# project_vodorezov_switch3.net
KiCad netlist of a schematic drawn in Altium Designer
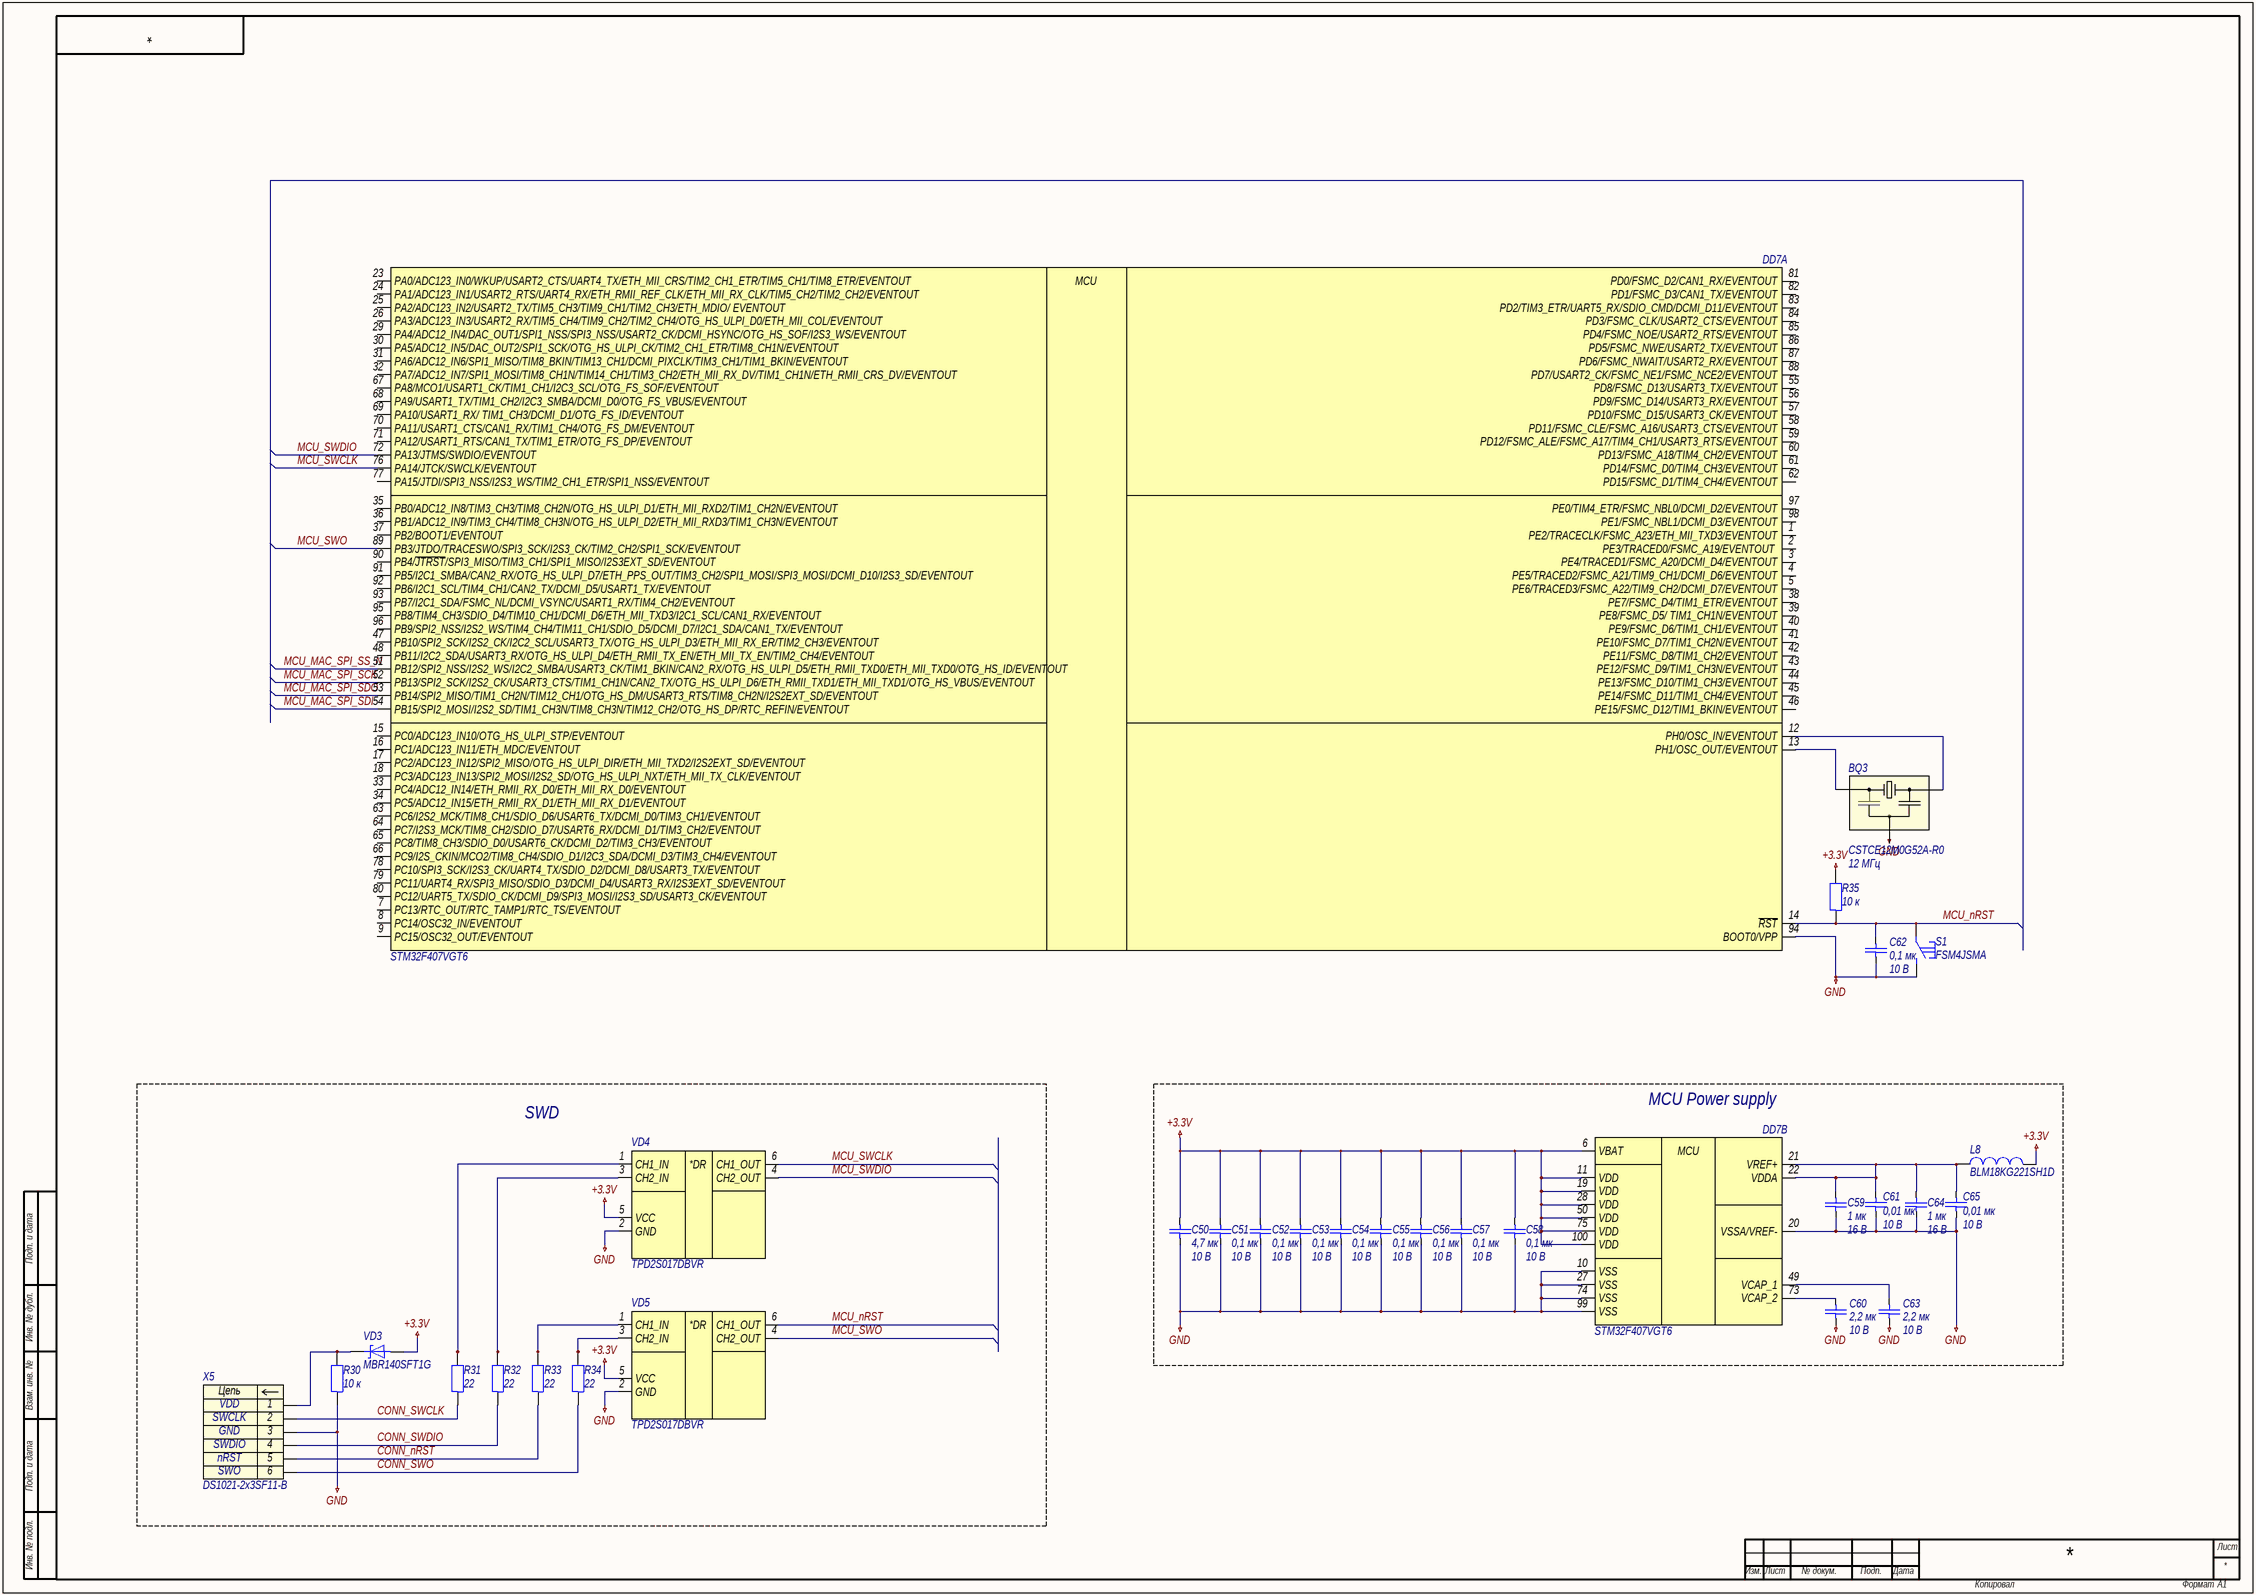
[diagram p0: project_vodorezov_switch3.SchDoc]

(export (version "E")
  (design (tool "Eeschema 10.0.6"))
  (components
    (comp (ref "BQ3")
      (value "CSTCE12M0G52A-R0")
      (footprint "CSTCE-3-P120-320X130X70")
      (description "=Описание")
      (fields (field (name "ЧАСТОТA") "12 МГц"))
      (libsource (lib "Database_Students") (part "CSTCE12M0G52A-R0"))
    )
    (comp (ref "C50")
      (value "4,7 мк")
      (footprint "C0603")
      (description "=Описание")
      (fields (field (name "НАПРЯЖЕНИЕ") "10 В"))
      (libsource (lib "Database_Students") (part "CAPACITOR-NONPOLAR"))
    )
    (comp (ref "C51")
      (value "0,1 мк")
      (footprint "C0402")
      (description "=Описание")
      (fields (field (name "НАПРЯЖЕНИЕ") "10 В"))
      (libsource (lib "Database_Students") (part "CAPACITOR-NONPOLAR"))
    )
    (comp (ref "C52")
      (value "0,1 мк")
      (footprint "C0402")
      (description "=Описание")
      (fields (field (name "НАПРЯЖЕНИЕ") "10 В"))
      (libsource (lib "Database_Students") (part "CAPACITOR-NONPOLAR"))
    )
    (comp (ref "C53")
      (value "0,1 мк")
      (footprint "C0402")
      (description "=Описание")
      (fields (field (name "НАПРЯЖЕНИЕ") "10 В"))
      (libsource (lib "Database_Students") (part "CAPACITOR-NONPOLAR"))
    )
    (comp (ref "C54")
      (value "0,1 мк")
      (footprint "C0402")
      (description "=Описание")
      (fields (field (name "НАПРЯЖЕНИЕ") "10 В"))
      (libsource (lib "Database_Students") (part "CAPACITOR-NONPOLAR"))
    )
    (comp (ref "C55")
      (value "0,1 мк")
      (footprint "C0402")
      (description "=Описание")
      (fields (field (name "НАПРЯЖЕНИЕ") "10 В"))
      (libsource (lib "Database_Students") (part "CAPACITOR-NONPOLAR"))
    )
    (comp (ref "C56")
      (value "0,1 мк")
      (footprint "C0402")
      (description "=Описание")
      (fields (field (name "НАПРЯЖЕНИЕ") "10 В"))
      (libsource (lib "Database_Students") (part "CAPACITOR-NONPOLAR"))
    )
    (comp (ref "C57")
      (value "0,1 мк")
      (footprint "C0402")
      (description "=Описание")
      (fields (field (name "НАПРЯЖЕНИЕ") "10 В"))
      (libsource (lib "Database_Students") (part "CAPACITOR-NONPOLAR"))
    )
    (comp (ref "C58")
      (value "0,1 мк")
      (footprint "C0402")
      (description "=Описание")
      (fields (field (name "НАПРЯЖЕНИЕ") "10 В"))
      (libsource (lib "Database_Students") (part "CAPACITOR-NONPOLAR"))
    )
    (comp (ref "C59")
      (value "1 мк")
      (footprint "C0603")
      (description "=Описание")
      (fields (field (name "НАПРЯЖЕНИЕ") "16 В"))
      (libsource (lib "Database_Students") (part "CAPACITOR-NONPOLAR"))
    )
    (comp (ref "C60")
      (value "2,2 мк")
      (footprint "C0603")
      (description "=Описание")
      (fields (field (name "НАПРЯЖЕНИЕ") "10 В"))
      (libsource (lib "Database_Students") (part "CAPACITOR-NONPOLAR"))
    )
    (comp (ref "C61")
      (value "0,01 мк")
      (footprint "C0603")
      (description "=Описание")
      (fields (field (name "НАПРЯЖЕНИЕ") "10 В"))
      (libsource (lib "Database_Students") (part "CAPACITOR-NONPOLAR"))
    )
    (comp (ref "C62")
      (value "0,1 мк")
      (footprint "C0603")
      (description "=Описание")
      (fields (field (name "НАПРЯЖЕНИЕ") "10 В"))
      (libsource (lib "Database_Students") (part "CAPACITOR-NONPOLAR"))
    )
    (comp (ref "C63")
      (value "2,2 мк")
      (footprint "C0603")
      (description "=Описание")
      (fields (field (name "НАПРЯЖЕНИЕ") "10 В"))
      (libsource (lib "Database_Students") (part "CAPACITOR-NONPOLAR"))
    )
    (comp (ref "C64")
      (value "1 мк")
      (footprint "C0603")
      (description "=Описание")
      (fields (field (name "НАПРЯЖЕНИЕ") "16 В"))
      (libsource (lib "Database_Students") (part "CAPACITOR-NONPOLAR"))
    )
    (comp (ref "C65")
      (value "0,01 мк")
      (footprint "C0603")
      (description "=Описание")
      (fields (field (name "НАПРЯЖЕНИЕ") "10 В"))
      (libsource (lib "Database_Students") (part "CAPACITOR-NONPOLAR"))
    )
    (comp (ref "DD7")
      (value "STM32F407VGT6")
      (footprint "LQFP-100-P50-1400X1400X160-L60X22")
      (description "=Описание")
      (libsource (lib "Database_Students") (part "STM32F407VGT6"))
    )
    (comp (ref "L8")
      (value "BLM18KG221SH1D")
      (footprint "BLM-2-0603")
      (description "=Описание")
      (libsource (lib "Database_Students") (part "FERRITE-BEAD"))
    )
    (comp (ref "R30")
      (value "10 к")
      (footprint "R0603")
      (description "=Описание")
      (libsource (lib "Database_Students") (part "RESISTOR-COMMON"))
    )
    (comp (ref "R31")
      (value "22")
      (footprint "R0603")
      (description "=Описание")
      (libsource (lib "Database_Students") (part "RESISTOR-COMMON"))
    )
    (comp (ref "R32")
      (value "22")
      (footprint "R0603")
      (description "=Описание")
      (libsource (lib "Database_Students") (part "RESISTOR-COMMON"))
    )
    (comp (ref "R33")
      (value "22")
      (footprint "R0603")
      (description "=Описание")
      (libsource (lib "Database_Students") (part "RESISTOR-COMMON"))
    )
    (comp (ref "R34")
      (value "22")
      (footprint "R0603")
      (description "=Описание")
      (libsource (lib "Database_Students") (part "RESISTOR-COMMON"))
    )
    (comp (ref "R35")
      (value "10 к")
      (footprint "R0603")
      (description "=Описание")
      (libsource (lib "Database_Students") (part "RESISTOR-COMMON"))
    )
    (comp (ref "S1")
      (value "FSM4JSMA")
      (footprint "FSM4JSMA")
      (description "=Описание")
      (libsource (lib "Database_Students") (part "BUTTON"))
    )
    (comp (ref "VD3")
      (value "MBR140SFT1G")
      (footprint "SOD-123FL-370X165X98")
      (description "=Описание")
      (libsource (lib "Database_Students") (part "DIODE-SCHOTTKY"))
    )
    (comp (ref "VD4")
      (value "TPD2S017DBVR")
      (footprint "SOT-23-6-P95-290X280X145")
      (description "=Описание")
      (libsource (lib "Database_Students") (part "TPD2S017DBVR"))
    )
    (comp (ref "VD5")
      (value "TPD2S017DBVR")
      (footprint "SOT-23-6-P95-290X280X145")
      (description "=Описание")
      (libsource (lib "Database_Students") (part "TPD2S017DBVR"))
    )
    (comp (ref "X5")
      (value "DS1021-2x3SF11-B")
      (footprint "DS1021-2X3SF11-B")
      (description "=Описание")
      (libsource (lib "Database_Students") (part "HEADER-6-PLG"))
    )
  )
  (nets
    (net (code "1") (name "+3.3V") (class "Default")
      (node (ref "C50") (pin "1") (pinfunction "1_1") (pintype "passive"))
      (node (ref "C51") (pin "1") (pinfunction "1_1") (pintype "passive"))
      (node (ref "C52") (pin "1") (pinfunction "1_1") (pintype "passive"))
      (node (ref "C53") (pin "1") (pinfunction "1_1") (pintype "passive"))
      (node (ref "C54") (pin "1") (pinfunction "1_1") (pintype "passive"))
      (node (ref "C55") (pin "1") (pinfunction "1_1") (pintype "passive"))
      (node (ref "C56") (pin "1") (pinfunction "1_1") (pintype "passive"))
      (node (ref "C57") (pin "1") (pinfunction "1_1") (pintype "passive"))
      (node (ref "C58") (pin "1") (pinfunction "1_1") (pintype "passive"))
      (node (ref "DD7") (pin "100") (pinfunction "VDD_100") (pintype "passive"))
      (node (ref "DD7") (pin "11") (pinfunction "VDD_11") (pintype "passive"))
      (node (ref "DD7") (pin "19") (pinfunction "VDD_19") (pintype "passive"))
      (node (ref "DD7") (pin "28") (pinfunction "VDD_28") (pintype "passive"))
      (node (ref "DD7") (pin "50") (pinfunction "VDD_50") (pintype "passive"))
      (node (ref "DD7") (pin "6") (pinfunction "VBAT_6") (pintype "passive"))
      (node (ref "DD7") (pin "75") (pinfunction "VDD_75") (pintype "passive"))
      (node (ref "L8") (pin "2") (pinfunction "2_2") (pintype "passive"))
      (node (ref "R35") (pin "2") (pinfunction "2_2") (pintype "passive"))
      (node (ref "VD3") (pin "2") (pinfunction "2_2") (pintype "passive"))
      (node (ref "VD4") (pin "5") (pinfunction "VCC_5") (pintype "passive"))
      (node (ref "VD5") (pin "5") (pinfunction "VCC_5") (pintype "passive"))
    )
    (net (code "2") (name "/CONN_SWCLK") (class "Default")
      (node (ref "R31") (pin "1") (pinfunction "1_1") (pintype "passive"))
      (node (ref "X5") (pin "2") (pinfunction "2_2") (pintype "passive"))
    )
    (net (code "3") (name "/CONN_SWDIO") (class "Default")
      (node (ref "R32") (pin "1") (pinfunction "1_1") (pintype "passive"))
      (node (ref "X5") (pin "4") (pinfunction "4_4") (pintype "passive"))
    )
    (net (code "4") (name "/CONN_SWO") (class "Default")
      (node (ref "R34") (pin "1") (pinfunction "1_1") (pintype "passive"))
      (node (ref "X5") (pin "6") (pinfunction "6_6") (pintype "passive"))
    )
    (net (code "5") (name "/CONN_nRST") (class "Default")
      (node (ref "R33") (pin "1") (pinfunction "1_1") (pintype "passive"))
      (node (ref "X5") (pin "5") (pinfunction "5_5") (pintype "passive"))
    )
    (net (code "6") (name "/MCU_MAC_SPI_SCK") (class "Default")
      (node (ref "DD7") (pin "52") (pinfunction "PB13/SPI2_SCK/I2S2_CK/USART3_CTS/TIM1_CH1N/CAN2_TX/OTG_HS_ULPI_D6/ETH_RMII_TXD1/ETH_MII_TXD1/OTG_HS_VBUS/EVENTOUT_52") (pintype "passive"))
    )
    (net (code "7") (name "/MCU_MAC_SPI_SDI") (class "Default")
      (node (ref "DD7") (pin "54") (pinfunction "PB15/SPI2_MOSI/I2S2_SD/TIM1_CH3N/TIM8_CH3N/TIM12_CH2/OTG_HS_DP/RTC_REFIN/EVENTOUT_54") (pintype "passive"))
    )
    (net (code "8") (name "/MCU_MAC_SPI_SDO") (class "Default")
      (node (ref "DD7") (pin "53") (pinfunction "PB14/SPI2_MISO/TIM1_CH2N/TIM12_CH1/OTG_HS_DM/USART3_RTS/TIM8_CH2N/I2S2EXT_SD/EVENTOUT_53") (pintype "passive"))
    )
    (net (code "9") (name "/MCU_MAC_SPI_SS_N") (class "Default")
      (node (ref "DD7") (pin "51") (pinfunction "PB12/SPI2_NSS/I2S2_WS/I2C2_SMBA/USART3_CK/TIM1_BKIN/CAN2_RX/OTG_HS_ULPI_D5/ETH_RMII_TXD0/ETH_MII_TXD0/OTG_HS_ID/EVENTOUT_51") (pintype "passive"))
    )
    (net (code "10") (name "/MCU_SWCLK") (class "Default")
      (node (ref "DD7") (pin "76") (pinfunction "PA14/JTCK/SWCLK/EVENTOUT_76") (pintype "passive"))
      (node (ref "VD4") (pin "6") (pinfunction "CH1_OUT_6") (pintype "passive"))
    )
    (net (code "11") (name "/MCU_SWDIO") (class "Default")
      (node (ref "DD7") (pin "72") (pinfunction "PA13/JTMS/SWDIO/EVENTOUT_72") (pintype "passive"))
      (node (ref "VD4") (pin "4") (pinfunction "CH2_OUT_4") (pintype "passive"))
    )
    (net (code "12") (name "/MCU_SWO") (class "Default")
      (node (ref "DD7") (pin "89") (pinfunction "PB3/JTDO/TRACESWO/SPI3_SCK/I2S3_CK/TIM2_CH2/SPI1_SCK/EVENTOUT_89") (pintype "passive"))
      (node (ref "VD5") (pin "4") (pinfunction "CH2_OUT_4") (pintype "passive"))
    )
    (net (code "13") (name "/MCU_nRST") (class "Default")
      (node (ref "C62") (pin "1") (pinfunction "1_1") (pintype "passive"))
      (node (ref "DD7") (pin "14") (pinfunction "~{RST}_14") (pintype "passive"))
      (node (ref "R35") (pin "1") (pinfunction "1_1") (pintype "passive"))
      (node (ref "S1") (pin "1") (pinfunction "1_1") (pintype "passive"))
      (node (ref "VD5") (pin "6") (pinfunction "CH1_OUT_6") (pintype "passive"))
    )
    (net (code "14") (name "GND") (class "Default")
      (node (ref "C50") (pin "2") (pinfunction "2_2") (pintype "passive"))
      (node (ref "C51") (pin "2") (pinfunction "2_2") (pintype "passive"))
      (node (ref "C52") (pin "2") (pinfunction "2_2") (pintype "passive"))
      (node (ref "C53") (pin "2") (pinfunction "2_2") (pintype "passive"))
      (node (ref "C54") (pin "2") (pinfunction "2_2") (pintype "passive"))
      (node (ref "C55") (pin "2") (pinfunction "2_2") (pintype "passive"))
      (node (ref "C56") (pin "2") (pinfunction "2_2") (pintype "passive"))
      (node (ref "C57") (pin "2") (pinfunction "2_2") (pintype "passive"))
      (node (ref "C58") (pin "2") (pinfunction "2_2") (pintype "passive"))
      (node (ref "C59") (pin "2") (pinfunction "2_2") (pintype "passive"))
      (node (ref "C60") (pin "2") (pinfunction "2_2") (pintype "passive"))
      (node (ref "C61") (pin "2") (pinfunction "2_2") (pintype "passive"))
      (node (ref "C62") (pin "2") (pinfunction "2_2") (pintype "passive"))
      (node (ref "C63") (pin "2") (pinfunction "2_2") (pintype "passive"))
      (node (ref "C64") (pin "2") (pinfunction "2_2") (pintype "passive"))
      (node (ref "C65") (pin "2") (pinfunction "2_2") (pintype "passive"))
      (node (ref "DD7") (pin "10") (pinfunction "VSS_10") (pintype "passive"))
      (node (ref "DD7") (pin "20") (pinfunction "VSSA/VREF-_20") (pintype "passive"))
      (node (ref "DD7") (pin "27") (pinfunction "VSS_27") (pintype "passive"))
      (node (ref "DD7") (pin "74") (pinfunction "VSS_74") (pintype "passive"))
      (node (ref "DD7") (pin "94") (pinfunction "BOOT0/VPP_94") (pintype "passive"))
      (node (ref "DD7") (pin "99") (pinfunction "VSS_99") (pintype "passive"))
      (node (ref "R30") (pin "1") (pinfunction "1_1") (pintype "passive"))
      (node (ref "S1") (pin "2") (pinfunction "2_2") (pintype "passive"))
      (node (ref "VD4") (pin "2") (pinfunction "GND_2") (pintype "passive"))
      (node (ref "VD5") (pin "2") (pinfunction "GND_2") (pintype "passive"))
      (node (ref "X5") (pin "3") (pinfunction "3_3") (pintype "passive"))
    )
    (net (code "15") (name "Net-(DD7A-PH0{slash}OSC_IN{slash}EVENTOUT)") (class "Default")
      (node (ref "BQ3") (pin "1") (pinfunction "1_1") (pintype "passive"))
      (node (ref "DD7") (pin "12") (pinfunction "PH0/OSC_IN/EVENTOUT_12") (pintype "passive"))
    )
    (net (code "16") (name "Net-(DD7A-PH1{slash}OSC_OUT{slash}EVENTOUT)") (class "Default")
      (node (ref "BQ3") (pin "3") (pinfunction "3_3") (pintype "passive"))
      (node (ref "DD7") (pin "13") (pinfunction "PH1/OSC_OUT/EVENTOUT_13") (pintype "passive"))
    )
    (net (code "17") (name "Net-(DD7B-VCAP_1)") (class "Default")
      (node (ref "C63") (pin "1") (pinfunction "1_1") (pintype "passive"))
      (node (ref "DD7") (pin "49") (pinfunction "VCAP_1_49") (pintype "passive"))
    )
    (net (code "18") (name "Net-(DD7B-VCAP_2)") (class "Default")
      (node (ref "C60") (pin "1") (pinfunction "1_1") (pintype "passive"))
      (node (ref "DD7") (pin "73") (pinfunction "VCAP_2_73") (pintype "passive"))
    )
    (net (code "19") (name "Net-(DD7B-VDDA)") (class "Default")
      (node (ref "C59") (pin "1") (pinfunction "1_1") (pintype "passive"))
      (node (ref "C61") (pin "1") (pinfunction "1_1") (pintype "passive"))
      (node (ref "C64") (pin "1") (pinfunction "1_1") (pintype "passive"))
      (node (ref "C65") (pin "1") (pinfunction "1_1") (pintype "passive"))
      (node (ref "DD7") (pin "21") (pinfunction "VREF+_21") (pintype "passive"))
      (node (ref "DD7") (pin "22") (pinfunction "VDDA_22") (pintype "passive"))
      (node (ref "L8") (pin "1") (pinfunction "1_1") (pintype "passive"))
    )
    (net (code "20") (name "Net-(R30-Pad2)") (class "Default")
      (node (ref "R30") (pin "2") (pinfunction "2_2") (pintype "passive"))
      (node (ref "VD3") (pin "1") (pinfunction "1_1") (pintype "passive"))
      (node (ref "X5") (pin "1") (pinfunction "1_1") (pintype "passive"))
    )
    (net (code "21") (name "Net-(VD4-CH1_IN)") (class "Default")
      (node (ref "R31") (pin "2") (pinfunction "2_2") (pintype "passive"))
      (node (ref "VD4") (pin "1") (pinfunction "CH1_IN_1") (pintype "passive"))
    )
    (net (code "22") (name "Net-(VD4-CH2_IN)") (class "Default")
      (node (ref "R32") (pin "2") (pinfunction "2_2") (pintype "passive"))
      (node (ref "VD4") (pin "3") (pinfunction "CH2_IN_3") (pintype "passive"))
    )
    (net (code "23") (name "Net-(VD5-CH1_IN)") (class "Default")
      (node (ref "R33") (pin "2") (pinfunction "2_2") (pintype "passive"))
      (node (ref "VD5") (pin "1") (pinfunction "CH1_IN_1") (pintype "passive"))
    )
    (net (code "24") (name "Net-(VD5-CH2_IN)") (class "Default")
      (node (ref "R34") (pin "2") (pinfunction "2_2") (pintype "passive"))
      (node (ref "VD5") (pin "3") (pinfunction "CH2_IN_3") (pintype "passive"))
    )
    (net (code "25") (name "unconnected-(BQ3-Pad2)") (class "Default")
      (node (ref "BQ3") (pin "2") (pinfunction "2_2") (pintype "passive"))
    )
    (net (code "26") (name "unconnected-(DD7A-PA0{slash}ADC123_IN0{slash}WKUP{slash}USART2_CTS{slash}UART4_TX{slash}ETH_MII_CRS{slash}TIM2_CH1_ETR{slash}TIM5_CH1{slash}TIM8_ETR{slash}EVENTOUT-Pad23)") (class "Default")
      (node (ref "DD7") (pin "23") (pinfunction "PA0/ADC123_IN0/WKUP/USART2_CTS/UART4_TX/ETH_MII_CRS/TIM2_CH1_ETR/TIM5_CH1/TIM8_ETR/EVENTOUT_23") (pintype "passive"))
    )
    (net (code "27") (name "unconnected-(DD7A-PA1{slash}ADC123_IN1{slash}USART2_RTS{slash}UART4_RX{slash}ETH_RMII_REF_CLK{slash}ETH_MII_RX_CLK{slash}TIM5_CH2{slash}TIM2_CH2{slash}EVENTOUT-Pad24)") (class "Default")
      (node (ref "DD7") (pin "24") (pinfunction "PA1/ADC123_IN1/USART2_RTS/UART4_RX/ETH_RMII_REF_CLK/ETH_MII_RX_CLK/TIM5_CH2/TIM2_CH2/EVENTOUT_24") (pintype "passive"))
    )
    (net (code "28") (name "unconnected-(DD7A-PA2{slash}ADC123_IN2{slash}USART2_TX{slash}TIM5_CH3{slash}TIM9_CH1{slash}TIM2_CH3{slash}ETH_MDIO{slash}_EVENTOUT-Pad25)") (class "Default")
      (node (ref "DD7") (pin "25") (pinfunction "PA2/ADC123_IN2/USART2_TX/TIM5_CH3/TIM9_CH1/TIM2_CH3/ETH_MDIO/_EVENTOUT_25") (pintype "passive"))
    )
    (net (code "29") (name "unconnected-(DD7A-PA3{slash}ADC123_IN3{slash}USART2_RX{slash}TIM5_CH4{slash}TIM9_CH2{slash}TIM2_CH4{slash}OTG_HS_ULPI_D0{slash}ETH_MII_COL{slash}EVENTOUT-Pad26)") (class "Default")
      (node (ref "DD7") (pin "26") (pinfunction "PA3/ADC123_IN3/USART2_RX/TIM5_CH4/TIM9_CH2/TIM2_CH4/OTG_HS_ULPI_D0/ETH_MII_COL/EVENTOUT_26") (pintype "passive"))
    )
    (net (code "30") (name "unconnected-(DD7A-PA4{slash}ADC12_IN4{slash}DAC_OUT1{slash}SPI1_NSS{slash}SPI3_NSS{slash}USART2_CK{slash}DCMI_HSYNC{slash}OTG_HS_SOF{slash}I2S3_WS{slash}EVENTOUT-Pad29)") (class "Default")
      (node (ref "DD7") (pin "29") (pinfunction "PA4/ADC12_IN4/DAC_OUT1/SPI1_NSS/SPI3_NSS/USART2_CK/DCMI_HSYNC/OTG_HS_SOF/I2S3_WS/EVENTOUT_29") (pintype "passive"))
    )
    (net (code "31") (name "unconnected-(DD7A-PA5{slash}ADC12_IN5{slash}DAC_OUT2{slash}SPI1_SCK{slash}OTG_HS_ULPI_CK{slash}TIM2_CH1_ETR{slash}TIM8_CH1N{slash}EVENTOUT-Pad30)") (class "Default")
      (node (ref "DD7") (pin "30") (pinfunction "PA5/ADC12_IN5/DAC_OUT2/SPI1_SCK/OTG_HS_ULPI_CK/TIM2_CH1_ETR/TIM8_CH1N/EVENTOUT_30") (pintype "passive"))
    )
    (net (code "32") (name "unconnected-(DD7A-PA6{slash}ADC12_IN6{slash}SPI1_MISO{slash}TIM8_BKIN{slash}TIM13_CH1{slash}DCMI_PIXCLK{slash}TIM3_CH1{slash}TIM1_BKIN{slash}EVENTOUT-Pad31)") (class "Default")
      (node (ref "DD7") (pin "31") (pinfunction "PA6/ADC12_IN6/SPI1_MISO/TIM8_BKIN/TIM13_CH1/DCMI_PIXCLK/TIM3_CH1/TIM1_BKIN/EVENTOUT_31") (pintype "passive"))
    )
    (net (code "33") (name "unconnected-(DD7A-PA7{slash}ADC12_IN7{slash}SPI1_MOSI{slash}TIM8_CH1N{slash}TIM14_CH1{slash}TIM3_CH2{slash}ETH_MII_RX_DV{slash}TIM1_CH1N{slash}ETH_RMII_CRS_DV{slash}EVENTOUT-Pad32)") (class "Default")
      (node (ref "DD7") (pin "32") (pinfunction "PA7/ADC12_IN7/SPI1_MOSI/TIM8_CH1N/TIM14_CH1/TIM3_CH2/ETH_MII_RX_DV/TIM1_CH1N/ETH_RMII_CRS_DV/EVENTOUT_32") (pintype "passive"))
    )
    (net (code "34") (name "unconnected-(DD7A-PA8{slash}MCO1{slash}USART1_CK{slash}TIM1_CH1{slash}I2C3_SCL{slash}OTG_FS_SOF{slash}EVENTOUT-Pad67)") (class "Default")
      (node (ref "DD7") (pin "67") (pinfunction "PA8/MCO1/USART1_CK/TIM1_CH1/I2C3_SCL/OTG_FS_SOF/EVENTOUT_67") (pintype "passive"))
    )
    (net (code "35") (name "unconnected-(DD7A-PA9{slash}USART1_TX{slash}TIM1_CH2{slash}I2C3_SMBA{slash}DCMI_D0{slash}OTG_FS_VBUS{slash}EVENTOUT-Pad68)") (class "Default")
      (node (ref "DD7") (pin "68") (pinfunction "PA9/USART1_TX/TIM1_CH2/I2C3_SMBA/DCMI_D0/OTG_FS_VBUS/EVENTOUT_68") (pintype "passive"))
    )
    (net (code "36") (name "unconnected-(DD7A-PA10{slash}USART1_RX{slash}_TIM1_CH3{slash}DCMI_D1{slash}OTG_FS_ID{slash}EVENTOUT-Pad69)") (class "Default")
      (node (ref "DD7") (pin "69") (pinfunction "PA10/USART1_RX/_TIM1_CH3/DCMI_D1/OTG_FS_ID/EVENTOUT_69") (pintype "passive"))
    )
    (net (code "37") (name "unconnected-(DD7A-PA11{slash}USART1_CTS{slash}CAN1_RX{slash}TIM1_CH4{slash}OTG_FS_DM{slash}EVENTOUT-Pad70)") (class "Default")
      (node (ref "DD7") (pin "70") (pinfunction "PA11/USART1_CTS/CAN1_RX/TIM1_CH4/OTG_FS_DM/EVENTOUT_70") (pintype "passive"))
    )
    (net (code "38") (name "unconnected-(DD7A-PA12{slash}USART1_RTS{slash}CAN1_TX{slash}TIM1_ETR{slash}OTG_FS_DP{slash}EVENTOUT-Pad71)") (class "Default")
      (node (ref "DD7") (pin "71") (pinfunction "PA12/USART1_RTS/CAN1_TX/TIM1_ETR/OTG_FS_DP/EVENTOUT_71") (pintype "passive"))
    )
    (net (code "39") (name "unconnected-(DD7A-PA15{slash}JTDI{slash}SPI3_NSS{slash}I2S3_WS{slash}TIM2_CH1_ETR{slash}SPI1_NSS{slash}EVENTOUT-Pad77)") (class "Default")
      (node (ref "DD7") (pin "77") (pinfunction "PA15/JTDI/SPI3_NSS/I2S3_WS/TIM2_CH1_ETR/SPI1_NSS/EVENTOUT_77") (pintype "passive"))
    )
    (net (code "40") (name "unconnected-(DD7A-PB0{slash}ADC12_IN8{slash}TIM3_CH3{slash}TIM8_CH2N{slash}OTG_HS_ULPI_D1{slash}ETH_MII_RXD2{slash}TIM1_CH2N{slash}EVENTOUT-Pad35)") (class "Default")
      (node (ref "DD7") (pin "35") (pinfunction "PB0/ADC12_IN8/TIM3_CH3/TIM8_CH2N/OTG_HS_ULPI_D1/ETH_MII_RXD2/TIM1_CH2N/EVENTOUT_35") (pintype "passive"))
    )
    (net (code "41") (name "unconnected-(DD7A-PB1{slash}ADC12_IN9{slash}TIM3_CH4{slash}TIM8_CH3N{slash}OTG_HS_ULPI_D2{slash}ETH_MII_RXD3{slash}TIM1_CH3N{slash}EVENTOUT-Pad36)") (class "Default")
      (node (ref "DD7") (pin "36") (pinfunction "PB1/ADC12_IN9/TIM3_CH4/TIM8_CH3N/OTG_HS_ULPI_D2/ETH_MII_RXD3/TIM1_CH3N/EVENTOUT_36") (pintype "passive"))
    )
    (net (code "42") (name "unconnected-(DD7A-PB2{slash}BOOT1{slash}EVENTOUT-Pad37)") (class "Default")
      (node (ref "DD7") (pin "37") (pinfunction "PB2/BOOT1/EVENTOUT_37") (pintype "passive"))
    )
    (net (code "43") (name "unconnected-(DD7A-PB4{slash}~{JTRST}{slash}SPI3_MISO{slash}TIM3_CH1{slash}SPI1_MISO{slash}I2S3EXT_SD{slash}EVENTOUT-Pad90)") (class "Default")
      (node (ref "DD7") (pin "90") (pinfunction "PB4/~{JTRST}/SPI3_MISO/TIM3_CH1/SPI1_MISO/I2S3EXT_SD/EVENTOUT_90") (pintype "passive"))
    )
    (net (code "44") (name "unconnected-(DD7A-PB5{slash}I2C1_SMBA{slash}CAN2_RX{slash}OTG_HS_ULPI_D7{slash}ETH_PPS_OUT{slash}TIM3_CH2{slash}SPI1_MOSI{slash}SPI3_MOSI{slash}DCMI_D10{slash}I2S3_SD{slash}EVENTOUT-Pad91)") (class "Default")
      (node (ref "DD7") (pin "91") (pinfunction "PB5/I2C1_SMBA/CAN2_RX/OTG_HS_ULPI_D7/ETH_PPS_OUT/TIM3_CH2/SPI1_MOSI/SPI3_MOSI/DCMI_D10/I2S3_SD/EVENTOUT_91") (pintype "passive"))
    )
    (net (code "45") (name "unconnected-(DD7A-PB6{slash}I2C1_SCL{slash}TIM4_CH1{slash}CAN2_TX{slash}DCMI_D5{slash}USART1_TX{slash}EVENTOUT-Pad92)") (class "Default")
      (node (ref "DD7") (pin "92") (pinfunction "PB6/I2C1_SCL/TIM4_CH1/CAN2_TX/DCMI_D5/USART1_TX/EVENTOUT_92") (pintype "passive"))
    )
    (net (code "46") (name "unconnected-(DD7A-PB7{slash}I2C1_SDA{slash}FSMC_NL{slash}DCMI_VSYNC{slash}USART1_RX{slash}TIM4_CH2{slash}EVENTOUT-Pad93)") (class "Default")
      (node (ref "DD7") (pin "93") (pinfunction "PB7/I2C1_SDA/FSMC_NL/DCMI_VSYNC/USART1_RX/TIM4_CH2/EVENTOUT_93") (pintype "passive"))
    )
    (net (code "47") (name "unconnected-(DD7A-PB8{slash}TIM4_CH3{slash}SDIO_D4{slash}TIM10_CH1{slash}DCMI_D6{slash}ETH_MII_TXD3{slash}I2C1_SCL{slash}CAN1_RX{slash}EVENTOUT-Pad95)") (class "Default")
      (node (ref "DD7") (pin "95") (pinfunction "PB8/TIM4_CH3/SDIO_D4/TIM10_CH1/DCMI_D6/ETH_MII_TXD3/I2C1_SCL/CAN1_RX/EVENTOUT_95") (pintype "passive"))
    )
    (net (code "48") (name "unconnected-(DD7A-PB9{slash}SPI2_NSS{slash}I2S2_WS{slash}TIM4_CH4{slash}TIM11_CH1{slash}SDIO_D5{slash}DCMI_D7{slash}I2C1_SDA{slash}CAN1_TX{slash}EVENTOUT-Pad96)") (class "Default")
      (node (ref "DD7") (pin "96") (pinfunction "PB9/SPI2_NSS/I2S2_WS/TIM4_CH4/TIM11_CH1/SDIO_D5/DCMI_D7/I2C1_SDA/CAN1_TX/EVENTOUT_96") (pintype "passive"))
    )
    (net (code "49") (name "unconnected-(DD7A-PB10{slash}SPI2_SCK{slash}I2S2_CK{slash}I2C2_SCL{slash}USART3_TX{slash}OTG_HS_ULPI_D3{slash}ETH_MII_RX_ER{slash}TIM2_CH3{slash}EVENTOUT-Pad47)") (class "Default")
      (node (ref "DD7") (pin "47") (pinfunction "PB10/SPI2_SCK/I2S2_CK/I2C2_SCL/USART3_TX/OTG_HS_ULPI_D3/ETH_MII_RX_ER/TIM2_CH3/EVENTOUT_47") (pintype "passive"))
    )
    (net (code "50") (name "unconnected-(DD7A-PB11{slash}I2C2_SDA{slash}USART3_RX{slash}OTG_HS_ULPI_D4{slash}ETH_RMII_TX_EN{slash}ETH_MII_TX_EN{slash}TIM2_CH4{slash}EVENTOUT-Pad48)") (class "Default")
      (node (ref "DD7") (pin "48") (pinfunction "PB11/I2C2_SDA/USART3_RX/OTG_HS_ULPI_D4/ETH_RMII_TX_EN/ETH_MII_TX_EN/TIM2_CH4/EVENTOUT_48") (pintype "passive"))
    )
    (net (code "51") (name "unconnected-(DD7A-PC0{slash}ADC123_IN10{slash}OTG_HS_ULPI_STP{slash}EVENTOUT-Pad15)") (class "Default")
      (node (ref "DD7") (pin "15") (pinfunction "PC0/ADC123_IN10/OTG_HS_ULPI_STP/EVENTOUT_15") (pintype "passive"))
    )
    (net (code "52") (name "unconnected-(DD7A-PC1{slash}ADC123_IN11{slash}ETH_MDC{slash}EVENTOUT-Pad16)") (class "Default")
      (node (ref "DD7") (pin "16") (pinfunction "PC1/ADC123_IN11/ETH_MDC/EVENTOUT_16") (pintype "passive"))
    )
    (net (code "53") (name "unconnected-(DD7A-PC2{slash}ADC123_IN12{slash}SPI2_MISO{slash}OTG_HS_ULPI_DIR{slash}ETH_MII_TXD2{slash}I2S2EXT_SD{slash}EVENTOUT-Pad17)") (class "Default")
      (node (ref "DD7") (pin "17") (pinfunction "PC2/ADC123_IN12/SPI2_MISO/OTG_HS_ULPI_DIR/ETH_MII_TXD2/I2S2EXT_SD/EVENTOUT_17") (pintype "passive"))
    )
    (net (code "54") (name "unconnected-(DD7A-PC3{slash}ADC123_IN13{slash}SPI2_MOSI{slash}I2S2_SD{slash}OTG_HS_ULPI_NXT{slash}ETH_MII_TX_CLK{slash}EVENTOUT-Pad18)") (class "Default")
      (node (ref "DD7") (pin "18") (pinfunction "PC3/ADC123_IN13/SPI2_MOSI/I2S2_SD/OTG_HS_ULPI_NXT/ETH_MII_TX_CLK/EVENTOUT_18") (pintype "passive"))
    )
    (net (code "55") (name "unconnected-(DD7A-PC4{slash}ADC12_IN14{slash}ETH_RMII_RX_D0{slash}ETH_MII_RX_D0{slash}EVENTOUT-Pad33)") (class "Default")
      (node (ref "DD7") (pin "33") (pinfunction "PC4/ADC12_IN14/ETH_RMII_RX_D0/ETH_MII_RX_D0/EVENTOUT_33") (pintype "passive"))
    )
    (net (code "56") (name "unconnected-(DD7A-PC5{slash}ADC12_IN15{slash}ETH_RMII_RX_D1{slash}ETH_MII_RX_D1{slash}EVENTOUT-Pad34)") (class "Default")
      (node (ref "DD7") (pin "34") (pinfunction "PC5/ADC12_IN15/ETH_RMII_RX_D1/ETH_MII_RX_D1/EVENTOUT_34") (pintype "passive"))
    )
    (net (code "57") (name "unconnected-(DD7A-PC6{slash}I2S2_MCK{slash}TIM8_CH1{slash}SDIO_D6{slash}USART6_TX{slash}DCMI_D0{slash}TIM3_CH1{slash}EVENTOUT-Pad63)") (class "Default")
      (node (ref "DD7") (pin "63") (pinfunction "PC6/I2S2_MCK/TIM8_CH1/SDIO_D6/USART6_TX/DCMI_D0/TIM3_CH1/EVENTOUT_63") (pintype "passive"))
    )
    (net (code "58") (name "unconnected-(DD7A-PC7{slash}I2S3_MCK{slash}TIM8_CH2{slash}SDIO_D7{slash}USART6_RX{slash}DCMI_D1{slash}TIM3_CH2{slash}EVENTOUT-Pad64)") (class "Default")
      (node (ref "DD7") (pin "64") (pinfunction "PC7/I2S3_MCK/TIM8_CH2/SDIO_D7/USART6_RX/DCMI_D1/TIM3_CH2/EVENTOUT_64") (pintype "passive"))
    )
    (net (code "59") (name "unconnected-(DD7A-PC8{slash}TIM8_CH3{slash}SDIO_D0{slash}USART6_CK{slash}DCMI_D2{slash}TIM3_CH3{slash}EVENTOUT-Pad65)") (class "Default")
      (node (ref "DD7") (pin "65") (pinfunction "PC8/TIM8_CH3/SDIO_D0/USART6_CK/DCMI_D2/TIM3_CH3/EVENTOUT_65") (pintype "passive"))
    )
    (net (code "60") (name "unconnected-(DD7A-PC9{slash}I2S_CKIN{slash}MCO2{slash}TIM8_CH4{slash}SDIO_D1{slash}I2C3_SDA{slash}DCMI_D3{slash}TIM3_CH4{slash}EVENTOUT-Pad66)") (class "Default")
      (node (ref "DD7") (pin "66") (pinfunction "PC9/I2S_CKIN/MCO2/TIM8_CH4/SDIO_D1/I2C3_SDA/DCMI_D3/TIM3_CH4/EVENTOUT_66") (pintype "passive"))
    )
    (net (code "61") (name "unconnected-(DD7A-PC10{slash}SPI3_SCK{slash}I2S3_CK{slash}UART4_TX{slash}SDIO_D2{slash}DCMI_D8{slash}USART3_TX{slash}EVENTOUT-Pad78)") (class "Default")
      (node (ref "DD7") (pin "78") (pinfunction "PC10/SPI3_SCK/I2S3_CK/UART4_TX/SDIO_D2/DCMI_D8/USART3_TX/EVENTOUT_78") (pintype "passive"))
    )
    (net (code "62") (name "unconnected-(DD7A-PC11{slash}UART4_RX{slash}SPI3_MISO{slash}SDIO_D3{slash}DCMI_D4{slash}USART3_RX{slash}I2S3EXT_SD{slash}EVENTOUT-Pad79)") (class "Default")
      (node (ref "DD7") (pin "79") (pinfunction "PC11/UART4_RX/SPI3_MISO/SDIO_D3/DCMI_D4/USART3_RX/I2S3EXT_SD/EVENTOUT_79") (pintype "passive"))
    )
    (net (code "63") (name "unconnected-(DD7A-PC12{slash}UART5_TX{slash}SDIO_CK{slash}DCMI_D9{slash}SPI3_MOSI{slash}I2S3_SD{slash}USART3_CK{slash}EVENTOUT-Pad80)") (class "Default")
      (node (ref "DD7") (pin "80") (pinfunction "PC12/UART5_TX/SDIO_CK/DCMI_D9/SPI3_MOSI/I2S3_SD/USART3_CK/EVENTOUT_80") (pintype "passive"))
    )
    (net (code "64") (name "unconnected-(DD7A-PC13{slash}RTC_OUT{slash}RTC_TAMP1{slash}RTC_TS{slash}EVENTOUT-Pad7)") (class "Default")
      (node (ref "DD7") (pin "7") (pinfunction "PC13/RTC_OUT/RTC_TAMP1/RTC_TS/EVENTOUT_7") (pintype "passive"))
    )
    (net (code "65") (name "unconnected-(DD7A-PC14{slash}OSC32_IN{slash}EVENTOUT-Pad8)") (class "Default")
      (node (ref "DD7") (pin "8") (pinfunction "PC14/OSC32_IN/EVENTOUT_8") (pintype "passive"))
    )
    (net (code "66") (name "unconnected-(DD7A-PC15{slash}OSC32_OUT{slash}EVENTOUT-Pad9)") (class "Default")
      (node (ref "DD7") (pin "9") (pinfunction "PC15/OSC32_OUT/EVENTOUT_9") (pintype "passive"))
    )
    (net (code "67") (name "unconnected-(DD7A-PD0{slash}FSMC_D2{slash}CAN1_RX{slash}EVENTOUT-Pad81)") (class "Default")
      (node (ref "DD7") (pin "81") (pinfunction "PD0/FSMC_D2/CAN1_RX/EVENTOUT_81") (pintype "passive"))
    )
    (net (code "68") (name "unconnected-(DD7A-PD1{slash}FSMC_D3{slash}CAN1_TX{slash}EVENTOUT-Pad82)") (class "Default")
      (node (ref "DD7") (pin "82") (pinfunction "PD1/FSMC_D3/CAN1_TX/EVENTOUT_82") (pintype "passive"))
    )
    (net (code "69") (name "unconnected-(DD7A-PD2{slash}TIM3_ETR{slash}UART5_RX{slash}SDIO_CMD{slash}DCMI_D11{slash}EVENTOUT-Pad83)") (class "Default")
      (node (ref "DD7") (pin "83") (pinfunction "PD2/TIM3_ETR/UART5_RX/SDIO_CMD/DCMI_D11/EVENTOUT_83") (pintype "passive"))
    )
    (net (code "70") (name "unconnected-(DD7A-PD3{slash}FSMC_CLK{slash}USART2_CTS{slash}EVENTOUT-Pad84)") (class "Default")
      (node (ref "DD7") (pin "84") (pinfunction "PD3/FSMC_CLK/USART2_CTS/EVENTOUT_84") (pintype "passive"))
    )
    (net (code "71") (name "unconnected-(DD7A-PD4{slash}FSMC_NOE{slash}USART2_RTS{slash}EVENTOUT-Pad85)") (class "Default")
      (node (ref "DD7") (pin "85") (pinfunction "PD4/FSMC_NOE/USART2_RTS/EVENTOUT_85") (pintype "passive"))
    )
    (net (code "72") (name "unconnected-(DD7A-PD5{slash}FSMC_NWE{slash}USART2_TX{slash}EVENTOUT-Pad86)") (class "Default")
      (node (ref "DD7") (pin "86") (pinfunction "PD5/FSMC_NWE/USART2_TX/EVENTOUT_86") (pintype "passive"))
    )
    (net (code "73") (name "unconnected-(DD7A-PD6{slash}FSMC_NWAIT{slash}USART2_RX{slash}EVENTOUT-Pad87)") (class "Default")
      (node (ref "DD7") (pin "87") (pinfunction "PD6/FSMC_NWAIT/USART2_RX/EVENTOUT_87") (pintype "passive"))
    )
    (net (code "74") (name "unconnected-(DD7A-PD7{slash}USART2_CK{slash}FSMC_NE1{slash}FSMC_NCE2{slash}EVENTOUT-Pad88)") (class "Default")
      (node (ref "DD7") (pin "88") (pinfunction "PD7/USART2_CK/FSMC_NE1/FSMC_NCE2/EVENTOUT_88") (pintype "passive"))
    )
    (net (code "75") (name "unconnected-(DD7A-PD8{slash}FSMC_D13{slash}USART3_TX{slash}EVENTOUT-Pad55)") (class "Default")
      (node (ref "DD7") (pin "55") (pinfunction "PD8/FSMC_D13/USART3_TX/EVENTOUT_55") (pintype "passive"))
    )
    (net (code "76") (name "unconnected-(DD7A-PD9{slash}FSMC_D14{slash}USART3_RX{slash}EVENTOUT-Pad56)") (class "Default")
      (node (ref "DD7") (pin "56") (pinfunction "PD9/FSMC_D14/USART3_RX/EVENTOUT_56") (pintype "passive"))
    )
    (net (code "77") (name "unconnected-(DD7A-PD10{slash}FSMC_D15{slash}USART3_CK{slash}EVENTOUT-Pad57)") (class "Default")
      (node (ref "DD7") (pin "57") (pinfunction "PD10/FSMC_D15/USART3_CK/EVENTOUT_57") (pintype "passive"))
    )
    (net (code "78") (name "unconnected-(DD7A-PD11{slash}FSMC_CLE{slash}FSMC_A16{slash}USART3_CTS{slash}EVENTOUT-Pad58)") (class "Default")
      (node (ref "DD7") (pin "58") (pinfunction "PD11/FSMC_CLE/FSMC_A16/USART3_CTS/EVENTOUT_58") (pintype "passive"))
    )
    (net (code "79") (name "unconnected-(DD7A-PD12{slash}FSMC_ALE{slash}FSMC_A17{slash}TIM4_CH1{slash}USART3_RTS{slash}EVENTOUT-Pad59)") (class "Default")
      (node (ref "DD7") (pin "59") (pinfunction "PD12/FSMC_ALE/FSMC_A17/TIM4_CH1/USART3_RTS/EVENTOUT_59") (pintype "passive"))
    )
    (net (code "80") (name "unconnected-(DD7A-PD13{slash}FSMC_A18{slash}TIM4_CH2{slash}EVENTOUT-Pad60)") (class "Default")
      (node (ref "DD7") (pin "60") (pinfunction "PD13/FSMC_A18/TIM4_CH2/EVENTOUT_60") (pintype "passive"))
    )
    (net (code "81") (name "unconnected-(DD7A-PD14{slash}FSMC_D0{slash}TIM4_CH3{slash}EVENTOUT-Pad61)") (class "Default")
      (node (ref "DD7") (pin "61") (pinfunction "PD14/FSMC_D0/TIM4_CH3/EVENTOUT_61") (pintype "passive"))
    )
    (net (code "82") (name "unconnected-(DD7A-PD15{slash}FSMC_D1{slash}TIM4_CH4{slash}EVENTOUT-Pad62)") (class "Default")
      (node (ref "DD7") (pin "62") (pinfunction "PD15/FSMC_D1/TIM4_CH4/EVENTOUT_62") (pintype "passive"))
    )
    (net (code "83") (name "unconnected-(DD7A-PE0{slash}TIM4_ETR{slash}FSMC_NBL0{slash}DCMI_D2{slash}EVENTOUT-Pad97)") (class "Default")
      (node (ref "DD7") (pin "97") (pinfunction "PE0/TIM4_ETR/FSMC_NBL0/DCMI_D2/EVENTOUT_97") (pintype "passive"))
    )
    (net (code "84") (name "unconnected-(DD7A-PE1{slash}FSMC_NBL1{slash}DCMI_D3{slash}EVENTOUT-Pad98)") (class "Default")
      (node (ref "DD7") (pin "98") (pinfunction "PE1/FSMC_NBL1/DCMI_D3/EVENTOUT_98") (pintype "passive"))
    )
    (net (code "85") (name "unconnected-(DD7A-PE2{slash}TRACECLK{slash}FSMC_A23{slash}ETH_MII_TXD3{slash}EVENTOUT-Pad1)") (class "Default")
      (node (ref "DD7") (pin "1") (pinfunction "PE2/TRACECLK/FSMC_A23/ETH_MII_TXD3/EVENTOUT_1") (pintype "passive"))
    )
    (net (code "86") (name "unconnected-(DD7A-PE3{slash}TRACED0{slash}FSMC_A19{slash}EVENTOUT-Pad2)") (class "Default")
      (node (ref "DD7") (pin "2") (pinfunction "PE3/TRACED0/FSMC_A19/EVENTOUT_2") (pintype "passive"))
    )
    (net (code "87") (name "unconnected-(DD7A-PE4{slash}TRACED1{slash}FSMC_A20{slash}DCMI_D4{slash}EVENTOUT-Pad3)") (class "Default")
      (node (ref "DD7") (pin "3") (pinfunction "PE4/TRACED1/FSMC_A20/DCMI_D4/EVENTOUT_3") (pintype "passive"))
    )
    (net (code "88") (name "unconnected-(DD7A-PE5{slash}TRACED2{slash}FSMC_A21{slash}TIM9_CH1{slash}DCMI_D6{slash}EVENTOUT-Pad4)") (class "Default")
      (node (ref "DD7") (pin "4") (pinfunction "PE5/TRACED2/FSMC_A21/TIM9_CH1/DCMI_D6/EVENTOUT_4") (pintype "passive"))
    )
    (net (code "89") (name "unconnected-(DD7A-PE6{slash}TRACED3{slash}FSMC_A22{slash}TIM9_CH2{slash}DCMI_D7{slash}EVENTOUT-Pad5)") (class "Default")
      (node (ref "DD7") (pin "5") (pinfunction "PE6/TRACED3/FSMC_A22/TIM9_CH2/DCMI_D7/EVENTOUT_5") (pintype "passive"))
    )
    (net (code "90") (name "unconnected-(DD7A-PE7{slash}FSMC_D4{slash}TIM1_ETR{slash}EVENTOUT-Pad38)") (class "Default")
      (node (ref "DD7") (pin "38") (pinfunction "PE7/FSMC_D4/TIM1_ETR/EVENTOUT_38") (pintype "passive"))
    )
    (net (code "91") (name "unconnected-(DD7A-PE8{slash}FSMC_D5{slash}_TIM1_CH1N{slash}EVENTOUT-Pad39)") (class "Default")
      (node (ref "DD7") (pin "39") (pinfunction "PE8/FSMC_D5/_TIM1_CH1N/EVENTOUT_39") (pintype "passive"))
    )
    (net (code "92") (name "unconnected-(DD7A-PE9{slash}FSMC_D6{slash}TIM1_CH1{slash}EVENTOUT-Pad40)") (class "Default")
      (node (ref "DD7") (pin "40") (pinfunction "PE9/FSMC_D6/TIM1_CH1/EVENTOUT_40") (pintype "passive"))
    )
    (net (code "93") (name "unconnected-(DD7A-PE10{slash}FSMC_D7{slash}TIM1_CH2N{slash}EVENTOUT-Pad41)") (class "Default")
      (node (ref "DD7") (pin "41") (pinfunction "PE10/FSMC_D7/TIM1_CH2N/EVENTOUT_41") (pintype "passive"))
    )
    (net (code "94") (name "unconnected-(DD7A-PE11{slash}FSMC_D8{slash}TIM1_CH2{slash}EVENTOUT-Pad42)") (class "Default")
      (node (ref "DD7") (pin "42") (pinfunction "PE11/FSMC_D8/TIM1_CH2/EVENTOUT_42") (pintype "passive"))
    )
    (net (code "95") (name "unconnected-(DD7A-PE12{slash}FSMC_D9{slash}TIM1_CH3N{slash}EVENTOUT-Pad43)") (class "Default")
      (node (ref "DD7") (pin "43") (pinfunction "PE12/FSMC_D9/TIM1_CH3N/EVENTOUT_43") (pintype "passive"))
    )
    (net (code "96") (name "unconnected-(DD7A-PE13{slash}FSMC_D10{slash}TIM1_CH3{slash}EVENTOUT-Pad44)") (class "Default")
      (node (ref "DD7") (pin "44") (pinfunction "PE13/FSMC_D10/TIM1_CH3/EVENTOUT_44") (pintype "passive"))
    )
    (net (code "97") (name "unconnected-(DD7A-PE14{slash}FSMC_D11{slash}TIM1_CH4{slash}EVENTOUT-Pad45)") (class "Default")
      (node (ref "DD7") (pin "45") (pinfunction "PE14/FSMC_D11/TIM1_CH4/EVENTOUT_45") (pintype "passive"))
    )
    (net (code "98") (name "unconnected-(DD7A-PE15{slash}FSMC_D12{slash}TIM1_BKIN{slash}EVENTOUT-Pad46)") (class "Default")
      (node (ref "DD7") (pin "46") (pinfunction "PE15/FSMC_D12/TIM1_BKIN/EVENTOUT_46") (pintype "passive"))
    )
  )
)
